# untitled.net
KiCad netlist of a schematic drawn in EAGLE
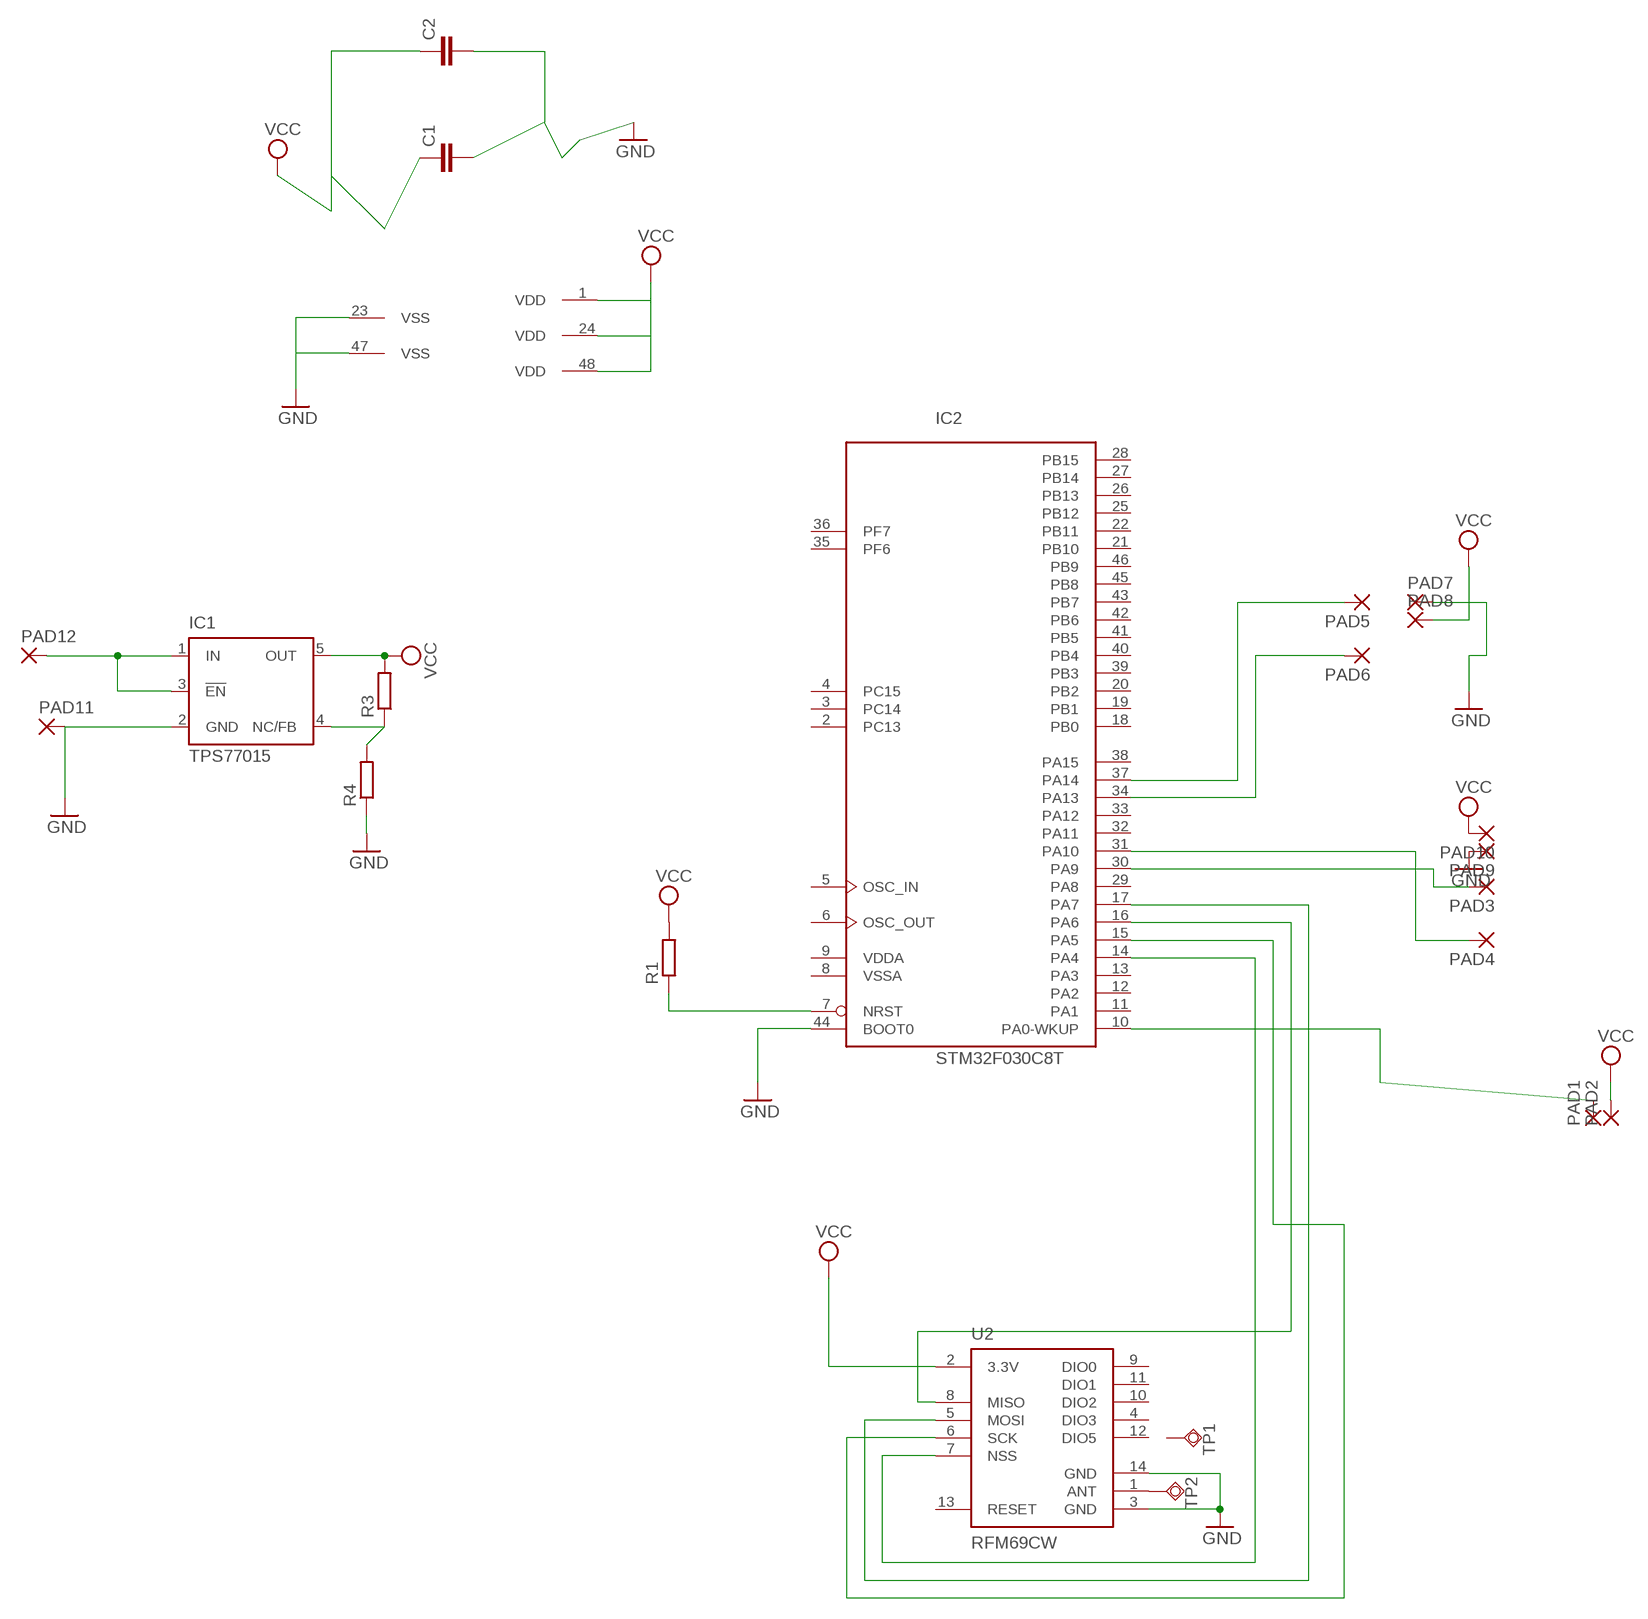
[diagram p0: schematic, sheet 1]

(export (version "E")
  (design (tool "Eeschema 10.0.6"))
  (components
    (comp (ref "C1")
      (value "C-EUC1206")
      (footprint "eagle-import:C1206")
      (libsource (lib "eagle-import") (part "C-EUC1206"))
    )
    (comp (ref "C2")
      (value "C-EUC1206")
      (footprint "eagle-import:C1206")
      (libsource (lib "eagle-import") (part "C-EUC1206"))
    )
    (comp (ref "IC1")
      (value "TPS77015")
      (footprint "eagle-import:SOT23-DBV")
      (fields (field (name "MF") "TEXAS INSTRUMENT CONNECTORS") (field (name "MPN") "TPS77015DBVT"))
      (libsource (lib "eagle-import") (part "TPS77015"))
    )
    (comp (ref "IC2")
      (value "STM32F030C8T")
      (footprint "eagle-import:LQFP48")
      (libsource (lib "eagle-import") (part "STM32F030CT8"))
    )
    (comp (ref "PAD1")
      (value "SMD2")
      (footprint "eagle-import:SMD1,27-2,54")
      (libsource (lib "eagle-import") (part "SMD2"))
    )
    (comp (ref "PAD2")
      (value "SMD2")
      (footprint "eagle-import:SMD1,27-2,54")
      (libsource (lib "eagle-import") (part "SMD2"))
    )
    (comp (ref "PAD3")
      (value "SMD2")
      (footprint "eagle-import:SMD1,27-2,54")
      (libsource (lib "eagle-import") (part "SMD2"))
    )
    (comp (ref "PAD4")
      (value "SMD2")
      (footprint "eagle-import:SMD1,27-2,54")
      (libsource (lib "eagle-import") (part "SMD2"))
    )
    (comp (ref "PAD5")
      (value "SMD2")
      (footprint "eagle-import:SMD1,27-2,54")
      (libsource (lib "eagle-import") (part "SMD2"))
    )
    (comp (ref "PAD6")
      (value "SMD2")
      (footprint "eagle-import:SMD1,27-2,54")
      (libsource (lib "eagle-import") (part "SMD2"))
    )
    (comp (ref "PAD7")
      (value "SMD2")
      (footprint "eagle-import:SMD1,27-2,54")
      (libsource (lib "eagle-import") (part "SMD2"))
    )
    (comp (ref "PAD8")
      (value "SMD2")
      (footprint "eagle-import:SMD1,27-2,54")
      (libsource (lib "eagle-import") (part "SMD2"))
    )
    (comp (ref "PAD9")
      (value "SMD2")
      (footprint "eagle-import:SMD1,27-2,54")
      (libsource (lib "eagle-import") (part "SMD2"))
    )
    (comp (ref "PAD10")
      (value "SMD2")
      (footprint "eagle-import:SMD1,27-2,54")
      (libsource (lib "eagle-import") (part "SMD2"))
    )
    (comp (ref "PAD11")
      (value "SMD2")
      (footprint "eagle-import:SMD1,27-2,54")
      (libsource (lib "eagle-import") (part "SMD2"))
    )
    (comp (ref "PAD12")
      (value "SMD2")
      (footprint "eagle-import:SMD1,27-2,54")
      (libsource (lib "eagle-import") (part "SMD2"))
    )
    (comp (ref "R1")
      (value "R-EU_M1206")
      (footprint "eagle-import:M1206")
      (libsource (lib "eagle-import") (part "R-EU_M1206"))
    )
    (comp (ref "R3")
      (value "R-EU_M0805")
      (footprint "eagle-import:M0805")
      (libsource (lib "eagle-import") (part "R-EU_M0805"))
    )
    (comp (ref "R4")
      (value "R-EU_M0805")
      (footprint "eagle-import:M0805")
      (libsource (lib "eagle-import") (part "R-EU_M0805"))
    )
    (comp (ref "TP1")
      (value "TPSQTP20SQ")
      (footprint "eagle-import:TP20SQ")
      (libsource (lib "eagle-import") (part "TPSQTP20SQ"))
    )
    (comp (ref "TP2")
      (value "TPSQTP20SQ")
      (footprint "eagle-import:TP20SQ")
      (libsource (lib "eagle-import") (part "TPSQTP20SQ"))
    )
    (comp (ref "U2")
      (value "RFM69CW")
      (footprint "eagle-import:RFM69CW-XXXS2")
      (libsource (lib "eagle-import") (part "RFM69CW"))
    )
  )
  (nets
    (net (code "1") (name "/VDDA") (class "Default")
      (node (ref "IC2") (pin "9") (pinfunction "VDDA_9") (pintype "power_in"))
    )
    (net (code "2") (name "/VSSA") (class "Default")
      (node (ref "IC2") (pin "8") (pinfunction "VSSA_8") (pintype "power_in"))
    )
    (net (code "3") (name "GND") (class "Default")
      (node (ref "C1") (pin "2") (pinfunction "2_2") (pintype "passive"))
      (node (ref "C2") (pin "2") (pinfunction "2_2") (pintype "passive"))
      (node (ref "IC1") (pin "2") (pinfunction "GND_2") (pintype "power_in"))
      (node (ref "IC2") (pin "23") (pinfunction "VSS_23") (pintype "power_in"))
      (node (ref "IC2") (pin "44") (pinfunction "BOOT0_44") (pintype "input"))
      (node (ref "IC2") (pin "47") (pinfunction "VSS_47") (pintype "power_in"))
      (node (ref "PAD11") (pin "1") (pinfunction "P_1") (pintype "passive"))
      (node (ref "PAD7") (pin "1") (pinfunction "P_1") (pintype "passive"))
      (node (ref "PAD9") (pin "1") (pinfunction "P_1") (pintype "passive"))
      (node (ref "R4") (pin "1") (pinfunction "1_1") (pintype "passive"))
      (node (ref "U2") (pin "14") (pinfunction "GND_14") (pintype "power_in"))
      (node (ref "U2") (pin "3") (pinfunction "GND_3") (pintype "power_in"))
    )
    (net (code "4") (name "Net-(IC1-IN)") (class "Default")
      (node (ref "IC1") (pin "1") (pinfunction "IN_1") (pintype "input"))
      (node (ref "IC1") (pin "3") (pinfunction "~{EN}_3") (pintype "input"))
      (node (ref "PAD12") (pin "1") (pinfunction "P_1") (pintype "passive"))
    )
    (net (code "5") (name "Net-(IC1-NC{slash}FB)") (class "Default")
      (node (ref "IC1") (pin "4") (pinfunction "NC/FB_4") (pintype "passive"))
      (node (ref "R3") (pin "1") (pinfunction "1_1") (pintype "passive"))
      (node (ref "R4") (pin "2") (pinfunction "2_2") (pintype "passive"))
    )
    (net (code "6") (name "Net-(IC2A-NRST)") (class "Default")
      (node (ref "IC2") (pin "7") (pinfunction "NRST_7") (pintype "bidirectional"))
      (node (ref "R1") (pin "1") (pinfunction "1_1") (pintype "passive"))
    )
    (net (code "7") (name "Net-(IC2A-PA0-WKUP)") (class "Default")
      (node (ref "IC2") (pin "10") (pinfunction "PA0-WKUP_10") (pintype "bidirectional"))
      (node (ref "PAD1") (pin "1") (pinfunction "P_1") (pintype "passive"))
    )
    (net (code "8") (name "Net-(IC2A-PA4)") (class "Default")
      (node (ref "IC2") (pin "14") (pinfunction "PA4_14") (pintype "bidirectional"))
      (node (ref "U2") (pin "7") (pinfunction "NSS_7") (pintype "input"))
    )
    (net (code "9") (name "Net-(IC2A-PA5)") (class "Default")
      (node (ref "IC2") (pin "15") (pinfunction "PA5_15") (pintype "bidirectional"))
      (node (ref "U2") (pin "6") (pinfunction "SCK_6") (pintype "input"))
    )
    (net (code "10") (name "Net-(IC2A-PA6)") (class "Default")
      (node (ref "IC2") (pin "16") (pinfunction "PA6_16") (pintype "bidirectional"))
      (node (ref "U2") (pin "8") (pinfunction "MISO_8") (pintype "bidirectional"))
    )
    (net (code "11") (name "Net-(IC2A-PA7)") (class "Default")
      (node (ref "IC2") (pin "17") (pinfunction "PA7_17") (pintype "bidirectional"))
      (node (ref "U2") (pin "5") (pinfunction "MOSI_5") (pintype "input"))
    )
    (net (code "12") (name "Net-(IC2A-PA9)") (class "Default")
      (node (ref "IC2") (pin "30") (pinfunction "PA9_30") (pintype "bidirectional"))
      (node (ref "PAD3") (pin "1") (pinfunction "P_1") (pintype "passive"))
    )
    (net (code "13") (name "Net-(IC2A-PA10)") (class "Default")
      (node (ref "IC2") (pin "31") (pinfunction "PA10_31") (pintype "bidirectional"))
      (node (ref "PAD4") (pin "1") (pinfunction "P_1") (pintype "passive"))
    )
    (net (code "14") (name "Net-(IC2A-PA13)") (class "Default")
      (node (ref "IC2") (pin "34") (pinfunction "PA13_34") (pintype "bidirectional"))
      (node (ref "PAD6") (pin "1") (pinfunction "P_1") (pintype "passive"))
    )
    (net (code "15") (name "Net-(IC2A-PA14)") (class "Default")
      (node (ref "IC2") (pin "37") (pinfunction "PA14_37") (pintype "bidirectional"))
      (node (ref "PAD5") (pin "1") (pinfunction "P_1") (pintype "passive"))
    )
    (net (code "16") (name "Net-(U2-ANT)") (class "Default")
      (node (ref "TP2") (pin "TP") (pinfunction "TP_TP") (pintype "input"))
      (node (ref "U2") (pin "1") (pinfunction "ANT_1") (pintype "passive"))
    )
    (net (code "17") (name "VCC") (class "Default")
      (node (ref "C1") (pin "1") (pinfunction "1_1") (pintype "passive"))
      (node (ref "C2") (pin "1") (pinfunction "1_1") (pintype "passive"))
      (node (ref "IC1") (pin "5") (pinfunction "OUT_5") (pintype "passive"))
      (node (ref "IC2") (pin "1") (pinfunction "VDD_1") (pintype "power_in"))
      (node (ref "IC2") (pin "24") (pinfunction "VDD_24") (pintype "power_in"))
      (node (ref "IC2") (pin "48") (pinfunction "VDD_48") (pintype "power_in"))
      (node (ref "PAD10") (pin "1") (pinfunction "P_1") (pintype "passive"))
      (node (ref "PAD2") (pin "1") (pinfunction "P_1") (pintype "passive"))
      (node (ref "PAD8") (pin "1") (pinfunction "P_1") (pintype "passive"))
      (node (ref "R1") (pin "2") (pinfunction "2_2") (pintype "passive"))
      (node (ref "R3") (pin "2") (pinfunction "2_2") (pintype "passive"))
      (node (ref "U2") (pin "2") (pinfunction "3.3V_2") (pintype "power_in"))
    )
    (net (code "18") (name "unconnected-(IC2A-OSC_IN-Pad5)") (class "Default")
      (node (ref "IC2") (pin "5") (pinfunction "OSC_IN_5") (pintype "bidirectional"))
    )
    (net (code "19") (name "unconnected-(IC2A-OSC_OUT-Pad6)") (class "Default")
      (node (ref "IC2") (pin "6") (pinfunction "OSC_OUT_6") (pintype "bidirectional"))
    )
    (net (code "20") (name "unconnected-(IC2A-PA1-Pad11)") (class "Default")
      (node (ref "IC2") (pin "11") (pinfunction "PA1_11") (pintype "bidirectional"))
    )
    (net (code "21") (name "unconnected-(IC2A-PA2-Pad12)") (class "Default")
      (node (ref "IC2") (pin "12") (pinfunction "PA2_12") (pintype "bidirectional"))
    )
    (net (code "22") (name "unconnected-(IC2A-PA3-Pad13)") (class "Default")
      (node (ref "IC2") (pin "13") (pinfunction "PA3_13") (pintype "bidirectional"))
    )
    (net (code "23") (name "unconnected-(IC2A-PA8-Pad29)") (class "Default")
      (node (ref "IC2") (pin "29") (pinfunction "PA8_29") (pintype "bidirectional"))
    )
    (net (code "24") (name "unconnected-(IC2A-PA11-Pad32)") (class "Default")
      (node (ref "IC2") (pin "32") (pinfunction "PA11_32") (pintype "bidirectional"))
    )
    (net (code "25") (name "unconnected-(IC2A-PA12-Pad33)") (class "Default")
      (node (ref "IC2") (pin "33") (pinfunction "PA12_33") (pintype "bidirectional"))
    )
    (net (code "26") (name "unconnected-(IC2A-PA15-Pad38)") (class "Default")
      (node (ref "IC2") (pin "38") (pinfunction "PA15_38") (pintype "bidirectional"))
    )
    (net (code "27") (name "unconnected-(IC2A-PB0-Pad18)") (class "Default")
      (node (ref "IC2") (pin "18") (pinfunction "PB0_18") (pintype "bidirectional"))
    )
    (net (code "28") (name "unconnected-(IC2A-PB1-Pad19)") (class "Default")
      (node (ref "IC2") (pin "19") (pinfunction "PB1_19") (pintype "bidirectional"))
    )
    (net (code "29") (name "unconnected-(IC2A-PB2-Pad20)") (class "Default")
      (node (ref "IC2") (pin "20") (pinfunction "PB2_20") (pintype "bidirectional"))
    )
    (net (code "30") (name "unconnected-(IC2A-PB3-Pad39)") (class "Default")
      (node (ref "IC2") (pin "39") (pinfunction "PB3_39") (pintype "bidirectional"))
    )
    (net (code "31") (name "unconnected-(IC2A-PB4-Pad40)") (class "Default")
      (node (ref "IC2") (pin "40") (pinfunction "PB4_40") (pintype "bidirectional"))
    )
    (net (code "32") (name "unconnected-(IC2A-PB5-Pad41)") (class "Default")
      (node (ref "IC2") (pin "41") (pinfunction "PB5_41") (pintype "bidirectional"))
    )
    (net (code "33") (name "unconnected-(IC2A-PB6-Pad42)") (class "Default")
      (node (ref "IC2") (pin "42") (pinfunction "PB6_42") (pintype "bidirectional"))
    )
    (net (code "34") (name "unconnected-(IC2A-PB7-Pad43)") (class "Default")
      (node (ref "IC2") (pin "43") (pinfunction "PB7_43") (pintype "bidirectional"))
    )
    (net (code "35") (name "unconnected-(IC2A-PB8-Pad45)") (class "Default")
      (node (ref "IC2") (pin "45") (pinfunction "PB8_45") (pintype "bidirectional"))
    )
    (net (code "36") (name "unconnected-(IC2A-PB9-Pad46)") (class "Default")
      (node (ref "IC2") (pin "46") (pinfunction "PB9_46") (pintype "bidirectional"))
    )
    (net (code "37") (name "unconnected-(IC2A-PB10-Pad21)") (class "Default")
      (node (ref "IC2") (pin "21") (pinfunction "PB10_21") (pintype "bidirectional"))
    )
    (net (code "38") (name "unconnected-(IC2A-PB11-Pad22)") (class "Default")
      (node (ref "IC2") (pin "22") (pinfunction "PB11_22") (pintype "bidirectional"))
    )
    (net (code "39") (name "unconnected-(IC2A-PB12-Pad25)") (class "Default")
      (node (ref "IC2") (pin "25") (pinfunction "PB12_25") (pintype "bidirectional"))
    )
    (net (code "40") (name "unconnected-(IC2A-PB13-Pad26)") (class "Default")
      (node (ref "IC2") (pin "26") (pinfunction "PB13_26") (pintype "bidirectional"))
    )
    (net (code "41") (name "unconnected-(IC2A-PB14-Pad27)") (class "Default")
      (node (ref "IC2") (pin "27") (pinfunction "PB14_27") (pintype "bidirectional"))
    )
    (net (code "42") (name "unconnected-(IC2A-PB15-Pad28)") (class "Default")
      (node (ref "IC2") (pin "28") (pinfunction "PB15_28") (pintype "bidirectional"))
    )
    (net (code "43") (name "unconnected-(IC2A-PC13-Pad2)") (class "Default")
      (node (ref "IC2") (pin "2") (pinfunction "PC13_2") (pintype "bidirectional"))
    )
    (net (code "44") (name "unconnected-(IC2A-PC14-Pad3)") (class "Default")
      (node (ref "IC2") (pin "3") (pinfunction "PC14_3") (pintype "bidirectional"))
    )
    (net (code "45") (name "unconnected-(IC2A-PC15-Pad4)") (class "Default")
      (node (ref "IC2") (pin "4") (pinfunction "PC15_4") (pintype "bidirectional"))
    )
    (net (code "46") (name "unconnected-(IC2A-PF6-Pad35)") (class "Default")
      (node (ref "IC2") (pin "35") (pinfunction "PF6_35") (pintype "bidirectional"))
    )
    (net (code "47") (name "unconnected-(IC2A-PF7-Pad36)") (class "Default")
      (node (ref "IC2") (pin "36") (pinfunction "PF7_36") (pintype "bidirectional"))
    )
    (net (code "48") (name "unconnected-(TP1-PadTP)") (class "Default")
      (node (ref "TP1") (pin "TP") (pinfunction "TP_TP") (pintype "input"))
    )
    (net (code "49") (name "unconnected-(U2-DIO0-Pad9)") (class "Default")
      (node (ref "U2") (pin "9") (pinfunction "DIO0_9") (pintype "bidirectional"))
    )
    (net (code "50") (name "unconnected-(U2-DIO1-Pad11)") (class "Default")
      (node (ref "U2") (pin "11") (pinfunction "DIO1_11") (pintype "bidirectional"))
    )
    (net (code "51") (name "unconnected-(U2-DIO2-Pad10)") (class "Default")
      (node (ref "U2") (pin "10") (pinfunction "DIO2_10") (pintype "bidirectional"))
    )
    (net (code "52") (name "unconnected-(U2-DIO3-Pad4)") (class "Default")
      (node (ref "U2") (pin "4") (pinfunction "DIO3_4") (pintype "bidirectional"))
    )
    (net (code "53") (name "unconnected-(U2-DIO5-Pad12)") (class "Default")
      (node (ref "U2") (pin "12") (pinfunction "DIO5_12") (pintype "bidirectional"))
    )
    (net (code "54") (name "unconnected-(U2-RESET-Pad13)") (class "Default")
      (node (ref "U2") (pin "13") (pinfunction "RESET_13") (pintype "input"))
    )
  )
)
